# trafficlight.net
KiCad netlist of a schematic drawn in EAGLE
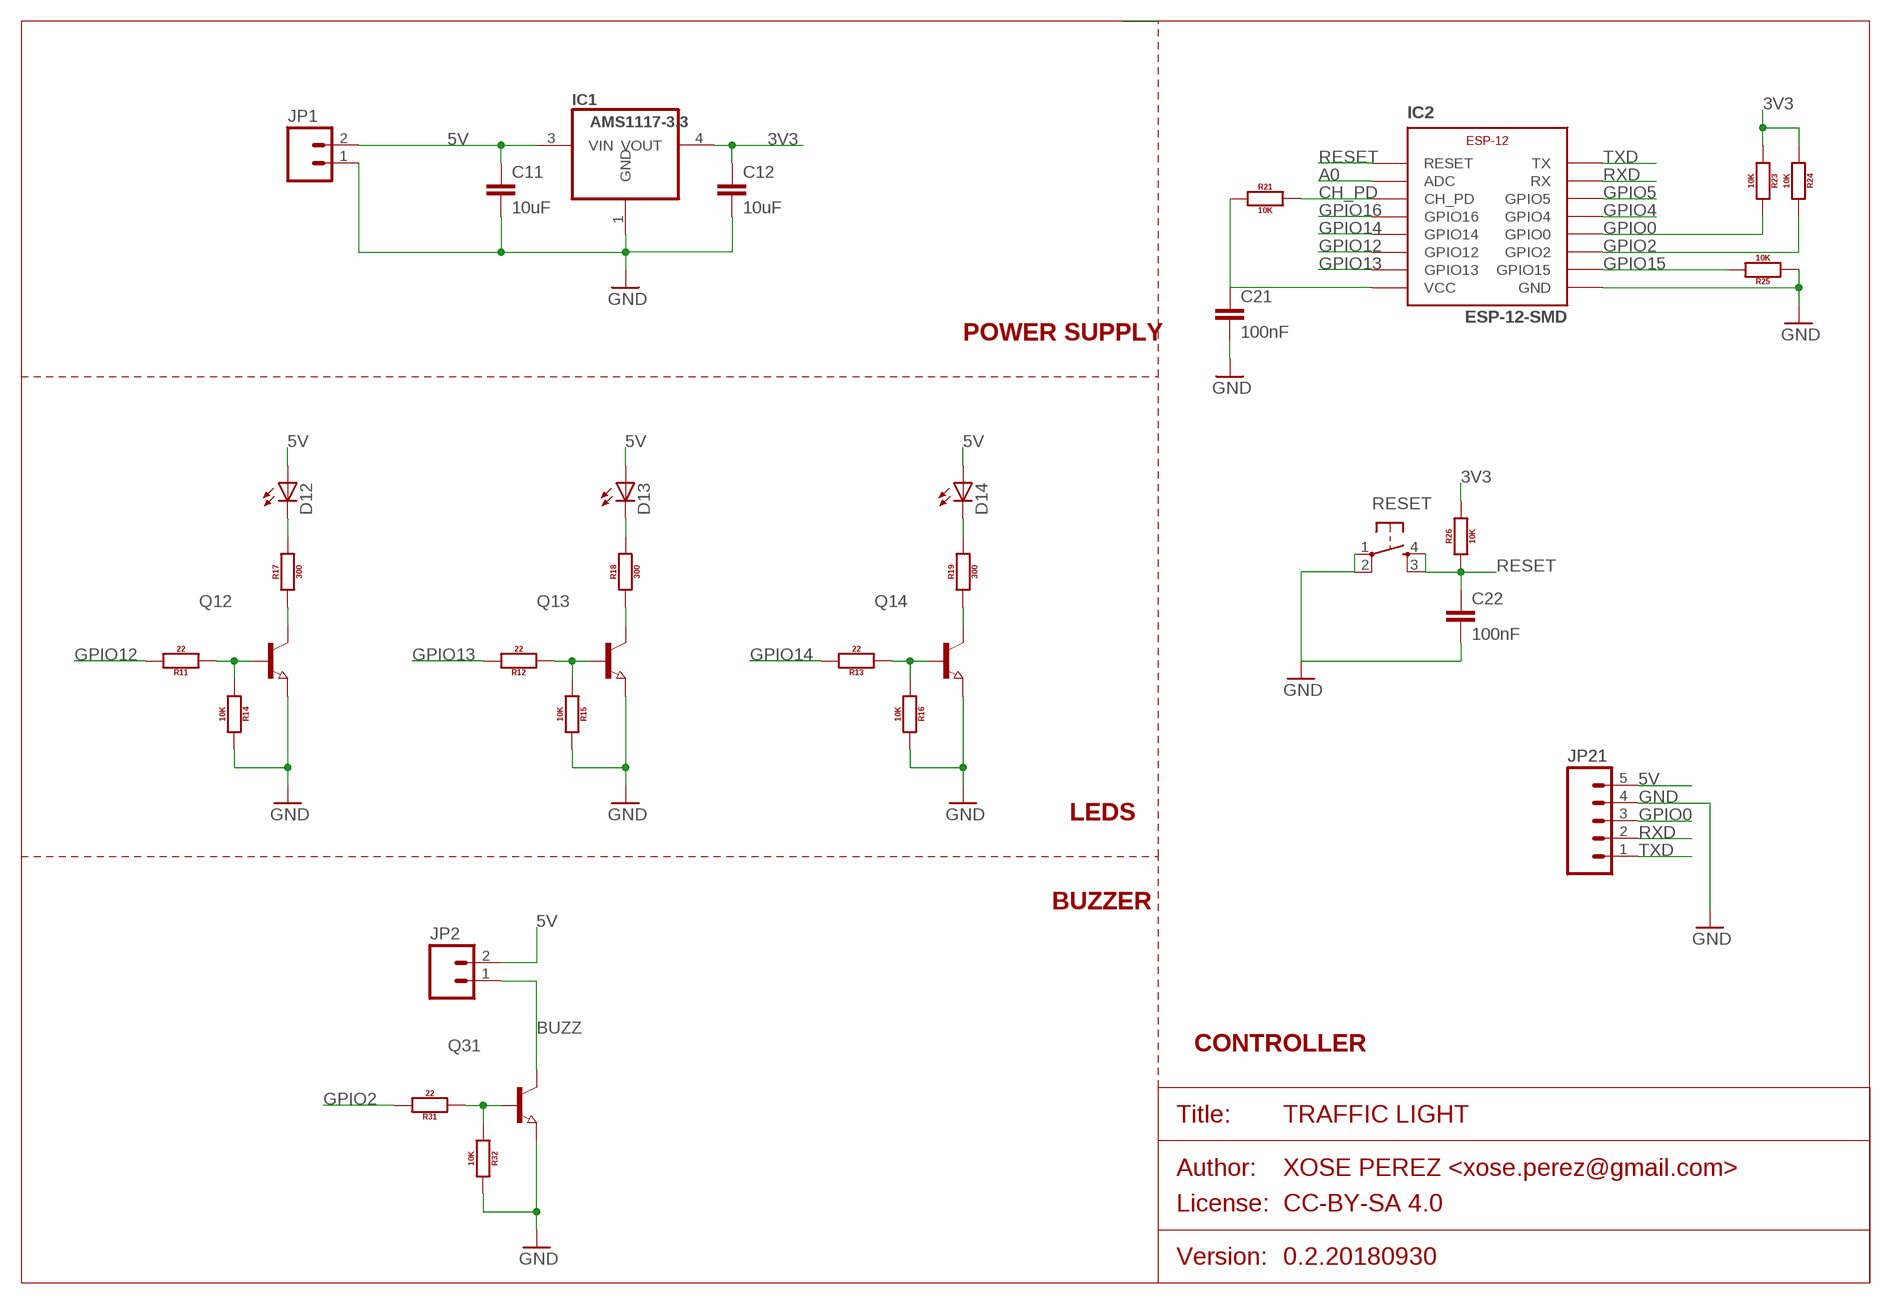
[diagram p0: schematic, sheet 1]

(export (version "E")
  (design (tool "Eeschema 10.0.6"))
  (components
    (comp (ref "C11")
      (value "10uF")
      (footprint "eagle-import:0805")
      (libsource (lib "eagle-import") (part "C-EU0805"))
    )
    (comp (ref "C12")
      (value "10uF")
      (footprint "eagle-import:0805")
      (libsource (lib "eagle-import") (part "C-EU0805"))
    )
    (comp (ref "C21")
      (value "100nF")
      (footprint "eagle-import:0805")
      (libsource (lib "eagle-import") (part "C-EU0805"))
    )
    (comp (ref "C22")
      (value "100nF")
      (footprint "eagle-import:0805")
      (libsource (lib "eagle-import") (part "C-EU0805"))
    )
    (comp (ref "D12")
      (value "LED5MM")
      (footprint "eagle-import:LED5MM")
      (libsource (lib "eagle-import") (part "LED5MM"))
    )
    (comp (ref "D13")
      (value "LED5MM")
      (footprint "eagle-import:LED5MM")
      (libsource (lib "eagle-import") (part "LED5MM"))
    )
    (comp (ref "D14")
      (value "LED5MM")
      (footprint "eagle-import:LED5MM")
      (libsource (lib "eagle-import") (part "LED5MM"))
    )
    (comp (ref "IC1")
      (value "AMS1117-3.3")
      (footprint "eagle-import:SOT223")
      (libsource (lib "eagle-import") (part "REG1117SOT223-2"))
    )
    (comp (ref "IC2")
      (value "ESP-12-SMD")
      (footprint "eagle-import:ESP-12-SMD")
      (libsource (lib "eagle-import") (part "ESP-12-SMD"))
    )
    (comp (ref "JP1")
      (value "M02PTH")
      (footprint "eagle-import:1X02")
      (libsource (lib "eagle-import") (part "M02PTH"))
    )
    (comp (ref "JP2")
      (value "M02PTH")
      (footprint "eagle-import:1X02")
      (libsource (lib "eagle-import") (part "M02PTH"))
    )
    (comp (ref "JP21")
      (value "M05PTH")
      (footprint "eagle-import:1X05")
      (libsource (lib "eagle-import") (part "M05PTH"))
    )
    (comp (ref "Q12")
      (value "NPN-TRANSISTOR_SOT23")
      (footprint "eagle-import:SOT23")
      (libsource (lib "eagle-import") (part "NPN-TRANSISTOR_SOT23"))
    )
    (comp (ref "Q13")
      (value "NPN-TRANSISTOR_SOT23")
      (footprint "eagle-import:SOT23")
      (libsource (lib "eagle-import") (part "NPN-TRANSISTOR_SOT23"))
    )
    (comp (ref "Q14")
      (value "NPN-TRANSISTOR_SOT23")
      (footprint "eagle-import:SOT23")
      (libsource (lib "eagle-import") (part "NPN-TRANSISTOR_SOT23"))
    )
    (comp (ref "Q31")
      (value "NPN-TRANSISTOR_SOT23")
      (footprint "eagle-import:SOT23")
      (libsource (lib "eagle-import") (part "NPN-TRANSISTOR_SOT23"))
    )
    (comp (ref "R11")
      (value "22")
      (footprint "eagle-import:0805")
      (libsource (lib "eagle-import") (part "RESISTOR0805"))
    )
    (comp (ref "R12")
      (value "22")
      (footprint "eagle-import:0805")
      (libsource (lib "eagle-import") (part "RESISTOR0805"))
    )
    (comp (ref "R13")
      (value "22")
      (footprint "eagle-import:0805")
      (libsource (lib "eagle-import") (part "RESISTOR0805"))
    )
    (comp (ref "R14")
      (value "10K")
      (footprint "eagle-import:0805")
      (libsource (lib "eagle-import") (part "RESISTOR0805"))
    )
    (comp (ref "R15")
      (value "10K")
      (footprint "eagle-import:0805")
      (libsource (lib "eagle-import") (part "RESISTOR0805"))
    )
    (comp (ref "R16")
      (value "10K")
      (footprint "eagle-import:0805")
      (libsource (lib "eagle-import") (part "RESISTOR0805"))
    )
    (comp (ref "R17")
      (value "300")
      (footprint "eagle-import:0805")
      (libsource (lib "eagle-import") (part "RESISTOR0805"))
    )
    (comp (ref "R18")
      (value "300")
      (footprint "eagle-import:0805")
      (libsource (lib "eagle-import") (part "RESISTOR0805"))
    )
    (comp (ref "R19")
      (value "300")
      (footprint "eagle-import:0805")
      (libsource (lib "eagle-import") (part "RESISTOR0805"))
    )
    (comp (ref "R21")
      (value "10K")
      (footprint "eagle-import:0805")
      (libsource (lib "eagle-import") (part "RESISTOR0805"))
    )
    (comp (ref "R23")
      (value "10K")
      (footprint "eagle-import:0805")
      (libsource (lib "eagle-import") (part "RESISTOR0805"))
    )
    (comp (ref "R24")
      (value "10K")
      (footprint "eagle-import:0805")
      (libsource (lib "eagle-import") (part "RESISTOR0805"))
    )
    (comp (ref "R25")
      (value "10K")
      (footprint "eagle-import:0805")
      (libsource (lib "eagle-import") (part "RESISTOR0805"))
    )
    (comp (ref "R26")
      (value "10K")
      (footprint "eagle-import:0805")
      (libsource (lib "eagle-import") (part "RESISTOR0805"))
    )
    (comp (ref "R31")
      (value "22")
      (footprint "eagle-import:0805")
      (libsource (lib "eagle-import") (part "RESISTOR0805"))
    )
    (comp (ref "R32")
      (value "10K")
      (footprint "eagle-import:0805")
      (libsource (lib "eagle-import") (part "RESISTOR0805"))
    )
    (comp (ref "RESET")
      (value "TACTILE_BUTTON_SMD")
      (footprint "eagle-import:TACTILE-BUTTON-SMD")
      (libsource (lib "eagle-import") (part "TACTILE_BUTTON_SMD"))
    )
  )
  (nets
    (net (code "1") (name "/3V3") (class "Default")
      (node (ref "C12") (pin "1") (pinfunction "1_1") (pintype "passive"))
      (node (ref "C21") (pin "1") (pinfunction "1_1") (pintype "passive"))
      (node (ref "IC1") (pin "4") (pinfunction "VOUT_4") (pintype "output"))
      (node (ref "IC2") (pin "VCC") (pinfunction "VCC_VCC") (pintype "bidirectional"))
      (node (ref "R21") (pin "1") (pinfunction "1_1") (pintype "passive"))
      (node (ref "R23") (pin "1") (pinfunction "1_1") (pintype "passive"))
      (node (ref "R24") (pin "1") (pinfunction "1_1") (pintype "passive"))
      (node (ref "R26") (pin "2") (pinfunction "2_2") (pintype "passive"))
    )
    (net (code "2") (name "/5V") (class "Default")
      (node (ref "C11") (pin "1") (pinfunction "1_1") (pintype "passive"))
      (node (ref "D12") (pin "A") (pinfunction "A_A") (pintype "passive"))
      (node (ref "D13") (pin "A") (pinfunction "A_A") (pintype "passive"))
      (node (ref "D14") (pin "A") (pinfunction "A_A") (pintype "passive"))
      (node (ref "IC1") (pin "3") (pinfunction "VIN_3") (pintype "input"))
      (node (ref "JP1") (pin "2") (pinfunction "2_2") (pintype "passive"))
      (node (ref "JP2") (pin "2") (pinfunction "2_2") (pintype "passive"))
      (node (ref "JP21") (pin "5") (pinfunction "5_5") (pintype "passive"))
    )
    (net (code "3") (name "/A0") (class "Default")
      (node (ref "IC2") (pin "ADC") (pinfunction "ADC_ADC") (pintype "bidirectional"))
    )
    (net (code "4") (name "/BUZZ") (class "Default")
      (node (ref "JP2") (pin "1") (pinfunction "1_1") (pintype "passive"))
      (node (ref "Q31") (pin "3") (pinfunction "C_3") (pintype "passive"))
    )
    (net (code "5") (name "/CH_PD") (class "Default")
      (node (ref "IC2") (pin "CH_PD") (pinfunction "CH_PD_CH_PD") (pintype "bidirectional"))
      (node (ref "R21") (pin "2") (pinfunction "2_2") (pintype "passive"))
    )
    (net (code "6") (name "/GPIO0") (class "Default")
      (node (ref "IC2") (pin "GPIO0") (pinfunction "GPIO0_GPIO0") (pintype "bidirectional"))
      (node (ref "JP21") (pin "3") (pinfunction "3_3") (pintype "passive"))
      (node (ref "R23") (pin "2") (pinfunction "2_2") (pintype "passive"))
    )
    (net (code "7") (name "/GPIO2") (class "Default")
      (node (ref "IC2") (pin "GPIO2") (pinfunction "GPIO2_GPIO2") (pintype "bidirectional"))
      (node (ref "R24") (pin "2") (pinfunction "2_2") (pintype "passive"))
      (node (ref "R31") (pin "2") (pinfunction "2_2") (pintype "passive"))
    )
    (net (code "8") (name "/GPIO4") (class "Default")
      (node (ref "IC2") (pin "GPIO4") (pinfunction "GPIO4_GPIO4") (pintype "bidirectional"))
    )
    (net (code "9") (name "/GPIO5") (class "Default")
      (node (ref "IC2") (pin "GPIO5") (pinfunction "GPIO5_GPIO5") (pintype "bidirectional"))
    )
    (net (code "10") (name "/GPIO12") (class "Default")
      (node (ref "IC2") (pin "GPIO12") (pinfunction "GPIO12_GPIO12") (pintype "bidirectional"))
      (node (ref "R11") (pin "2") (pinfunction "2_2") (pintype "passive"))
    )
    (net (code "11") (name "/GPIO13") (class "Default")
      (node (ref "IC2") (pin "GPIO13") (pinfunction "GPIO13_GPIO13") (pintype "bidirectional"))
      (node (ref "R12") (pin "2") (pinfunction "2_2") (pintype "passive"))
    )
    (net (code "12") (name "/GPIO14") (class "Default")
      (node (ref "IC2") (pin "GPIO14") (pinfunction "GPIO14_GPIO14") (pintype "bidirectional"))
      (node (ref "R13") (pin "2") (pinfunction "2_2") (pintype "passive"))
    )
    (net (code "13") (name "/GPIO15") (class "Default")
      (node (ref "IC2") (pin "GPIO15") (pinfunction "GPIO15_GPIO15") (pintype "bidirectional"))
      (node (ref "R25") (pin "2") (pinfunction "2_2") (pintype "passive"))
    )
    (net (code "14") (name "/GPIO16") (class "Default")
      (node (ref "IC2") (pin "GPIO16") (pinfunction "GPIO16_GPIO16") (pintype "bidirectional"))
    )
    (net (code "15") (name "/RESET") (class "Default")
      (node (ref "C22") (pin "1") (pinfunction "1_1") (pintype "passive"))
      (node (ref "IC2") (pin "RESET") (pinfunction "RESET_RESET") (pintype "bidirectional"))
      (node (ref "R26") (pin "1") (pinfunction "1_1") (pintype "passive"))
      (node (ref "RESET") (pin "3") (pinfunction "SWB2_3") (pintype "passive"))
      (node (ref "RESET") (pin "4") (pinfunction "SWA2_4") (pintype "passive"))
    )
    (net (code "16") (name "/RXD") (class "Default")
      (node (ref "IC2") (pin "RX") (pinfunction "RX_RX") (pintype "bidirectional"))
      (node (ref "JP21") (pin "2") (pinfunction "2_2") (pintype "passive"))
    )
    (net (code "17") (name "/TXD") (class "Default")
      (node (ref "IC2") (pin "TX") (pinfunction "TX_TX") (pintype "bidirectional"))
      (node (ref "JP21") (pin "1") (pinfunction "1_1") (pintype "passive"))
    )
    (net (code "18") (name "GND") (class "Default")
      (node (ref "C11") (pin "2") (pinfunction "2_2") (pintype "passive"))
      (node (ref "C12") (pin "2") (pinfunction "2_2") (pintype "passive"))
      (node (ref "C21") (pin "2") (pinfunction "2_2") (pintype "passive"))
      (node (ref "C22") (pin "2") (pinfunction "2_2") (pintype "passive"))
      (node (ref "IC1") (pin "1") (pinfunction "GND_1") (pintype "power_in"))
      (node (ref "IC2") (pin "GND") (pinfunction "GND_GND") (pintype "bidirectional"))
      (node (ref "JP1") (pin "1") (pinfunction "1_1") (pintype "passive"))
      (node (ref "JP21") (pin "4") (pinfunction "4_4") (pintype "passive"))
      (node (ref "Q12") (pin "2") (pinfunction "E_2") (pintype "passive"))
      (node (ref "Q13") (pin "2") (pinfunction "E_2") (pintype "passive"))
      (node (ref "Q14") (pin "2") (pinfunction "E_2") (pintype "passive"))
      (node (ref "Q31") (pin "2") (pinfunction "E_2") (pintype "passive"))
      (node (ref "R14") (pin "2") (pinfunction "2_2") (pintype "passive"))
      (node (ref "R15") (pin "2") (pinfunction "2_2") (pintype "passive"))
      (node (ref "R16") (pin "2") (pinfunction "2_2") (pintype "passive"))
      (node (ref "R25") (pin "1") (pinfunction "1_1") (pintype "passive"))
      (node (ref "R32") (pin "2") (pinfunction "2_2") (pintype "passive"))
      (node (ref "RESET") (pin "1") (pinfunction "SWA1_1") (pintype "passive"))
      (node (ref "RESET") (pin "2") (pinfunction "SWB1_2") (pintype "passive"))
    )
    (net (code "19") (name "Net-(D12-C)") (class "Default")
      (node (ref "D12") (pin "K") (pinfunction "C_K") (pintype "passive"))
      (node (ref "R17") (pin "2") (pinfunction "2_2") (pintype "passive"))
    )
    (net (code "20") (name "Net-(D13-C)") (class "Default")
      (node (ref "D13") (pin "K") (pinfunction "C_K") (pintype "passive"))
      (node (ref "R18") (pin "2") (pinfunction "2_2") (pintype "passive"))
    )
    (net (code "21") (name "Net-(D14-C)") (class "Default")
      (node (ref "D14") (pin "K") (pinfunction "C_K") (pintype "passive"))
      (node (ref "R19") (pin "2") (pinfunction "2_2") (pintype "passive"))
    )
    (net (code "22") (name "Net-(Q12-B)") (class "Default")
      (node (ref "Q12") (pin "1") (pinfunction "B_1") (pintype "passive"))
      (node (ref "R11") (pin "1") (pinfunction "1_1") (pintype "passive"))
      (node (ref "R14") (pin "1") (pinfunction "1_1") (pintype "passive"))
    )
    (net (code "23") (name "Net-(Q12-C)") (class "Default")
      (node (ref "Q12") (pin "3") (pinfunction "C_3") (pintype "passive"))
      (node (ref "R17") (pin "1") (pinfunction "1_1") (pintype "passive"))
    )
    (net (code "24") (name "Net-(Q13-B)") (class "Default")
      (node (ref "Q13") (pin "1") (pinfunction "B_1") (pintype "passive"))
      (node (ref "R12") (pin "1") (pinfunction "1_1") (pintype "passive"))
      (node (ref "R15") (pin "1") (pinfunction "1_1") (pintype "passive"))
    )
    (net (code "25") (name "Net-(Q13-C)") (class "Default")
      (node (ref "Q13") (pin "3") (pinfunction "C_3") (pintype "passive"))
      (node (ref "R18") (pin "1") (pinfunction "1_1") (pintype "passive"))
    )
    (net (code "26") (name "Net-(Q14-B)") (class "Default")
      (node (ref "Q14") (pin "1") (pinfunction "B_1") (pintype "passive"))
      (node (ref "R13") (pin "1") (pinfunction "1_1") (pintype "passive"))
      (node (ref "R16") (pin "1") (pinfunction "1_1") (pintype "passive"))
    )
    (net (code "27") (name "Net-(Q14-C)") (class "Default")
      (node (ref "Q14") (pin "3") (pinfunction "C_3") (pintype "passive"))
      (node (ref "R19") (pin "1") (pinfunction "1_1") (pintype "passive"))
    )
    (net (code "28") (name "Net-(Q31-B)") (class "Default")
      (node (ref "Q31") (pin "1") (pinfunction "B_1") (pintype "passive"))
      (node (ref "R31") (pin "1") (pinfunction "1_1") (pintype "passive"))
      (node (ref "R32") (pin "1") (pinfunction "1_1") (pintype "passive"))
    )
  )
)
